# Battery_Charger.net
KiCad netlist of a schematic drawn in Altium Designer
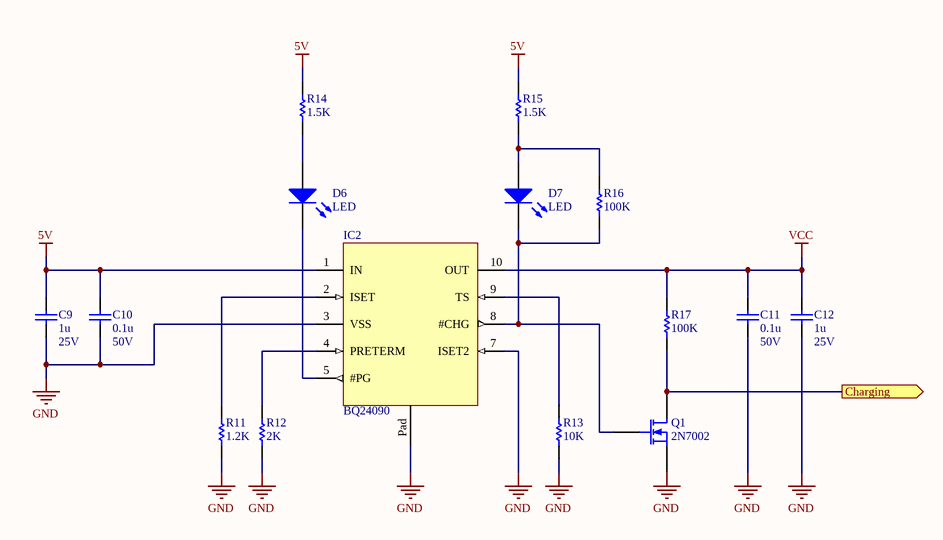
[diagram p0: Battery Charger.SchDoc]

(export (version "E")
  (design (tool "Eeschema 10.0.6"))
  (components
    (comp (ref "C9")
      (value "1u")
      (footprint "C1206")
      (description "Capacitor")
      (fields (field (name "RATED VOLTAGE") "25V"))
      (libsource (lib "Common Devices") (part "Capacitor"))
    )
    (comp (ref "C10")
      (value "0.1u")
      (footprint "C1206")
      (description "Capacitor")
      (fields (field (name "RATED VOLTAGE") "50V"))
      (libsource (lib "Common Devices") (part "Capacitor"))
    )
    (comp (ref "C11")
      (value "0.1u")
      (footprint "C1206")
      (description "Capacitor")
      (fields (field (name "RATED VOLTAGE") "50V"))
      (libsource (lib "Common Devices") (part "Capacitor"))
    )
    (comp (ref "C12")
      (value "1u")
      (footprint "C1206")
      (description "Capacitor")
      (fields (field (name "RATED VOLTAGE") "25V"))
      (libsource (lib "Common Devices") (part "Capacitor"))
    )
    (comp (ref "D6") (value "LED") (footprint "LED3015M") (libsource (lib "Common Devices") (part "LED")))
    (comp (ref "D7") (value "LED") (footprint "LED3015M") (libsource (lib "Common Devices") (part "LED")))
    (comp (ref "IC2")
      (value "BQ24090")
      (footprint "TSSOP50P490X110_HS-11N")
      (description "Battery Charger, Single Cell Li-Ion/LiPo, 1A")
      (libsource (lib "Docking Station") (part "BQ24090"))
    )
    (comp (ref "Q1")
      (value "2N7002")
      (footprint "SOT65P210X110-3N")
      (description "Transistor, MOSFET, N-Channel, 60V, 300mA")
      (libsource (lib "Common Devices") (part "2N7002"))
    )
    (comp (ref "R11")
      (value "1.2K")
      (footprint "R1206")
      (description "Resistor")
      (libsource (lib "Common Devices") (part "Resistor"))
    )
    (comp (ref "R12")
      (value "2K")
      (footprint "R1206")
      (description "Resistor")
      (libsource (lib "Common Devices") (part "Resistor"))
    )
    (comp (ref "R13")
      (value "10K")
      (footprint "R1206")
      (description "Resistor")
      (libsource (lib "Common Devices") (part "Resistor"))
    )
    (comp (ref "R14")
      (value "1.5K")
      (footprint "R1206")
      (description "Resistor")
      (libsource (lib "Common Devices") (part "Resistor"))
    )
    (comp (ref "R15")
      (value "1.5K")
      (footprint "R1206")
      (description "Resistor")
      (libsource (lib "Common Devices") (part "Resistor"))
    )
    (comp (ref "R16")
      (value "100K")
      (footprint "R1206")
      (description "Resistor")
      (libsource (lib "Common Devices") (part "Resistor"))
    )
    (comp (ref "R17")
      (value "100K")
      (footprint "R1206")
      (description "Resistor")
      (libsource (lib "Common Devices") (part "Resistor"))
    )
  )
  (nets
    (net (code "1") (name "/Charging") (class "Default")
      (node (ref "Q1") (pin "3") (pinfunction "D_3") (pintype "passive"))
      (node (ref "R17") (pin "1") (pinfunction "1_1") (pintype "passive"))
    )
    (net (code "2") (name "5V") (class "Default")
      (node (ref "C10") (pin "2") (pinfunction "2_2") (pintype "passive"))
      (node (ref "C9") (pin "2") (pinfunction "2_2") (pintype "passive"))
      (node (ref "IC2") (pin "1") (pinfunction "IN_1") (pintype "power_in"))
      (node (ref "R14") (pin "2") (pinfunction "2_2") (pintype "passive"))
      (node (ref "R15") (pin "2") (pinfunction "2_2") (pintype "passive"))
    )
    (net (code "3") (name "GND") (class "Default")
      (node (ref "C10") (pin "1") (pinfunction "1_1") (pintype "passive"))
      (node (ref "C11") (pin "1") (pinfunction "1_1") (pintype "passive"))
      (node (ref "C12") (pin "1") (pinfunction "1_1") (pintype "passive"))
      (node (ref "C9") (pin "1") (pinfunction "1_1") (pintype "passive"))
      (node (ref "IC2") (pin "3") (pinfunction "VSS_3") (pintype "power_in"))
      (node (ref "IC2") (pin "7") (pinfunction "ISET2_7") (pintype "input"))
      (node (ref "IC2") (pin "Pad") (pinfunction "Thermal_Pad") (pintype "passive"))
      (node (ref "Q1") (pin "2") (pinfunction "S_2") (pintype "passive"))
      (node (ref "R11") (pin "1") (pinfunction "1_1") (pintype "passive"))
      (node (ref "R12") (pin "1") (pinfunction "1_1") (pintype "passive"))
      (node (ref "R13") (pin "1") (pinfunction "1_1") (pintype "passive"))
    )
    (net (code "4") (name "Net-(D6-A)") (class "Default")
      (node (ref "D6") (pin "1") (pinfunction "A_1") (pintype "passive"))
      (node (ref "R14") (pin "1") (pinfunction "1_1") (pintype "passive"))
    )
    (net (code "5") (name "Net-(D6-K)") (class "Default")
      (node (ref "D6") (pin "2") (pinfunction "K_2") (pintype "passive"))
      (node (ref "IC2") (pin "5") (pinfunction "#PG_5") (pintype "output"))
    )
    (net (code "6") (name "Net-(D7-A)") (class "Default")
      (node (ref "D7") (pin "1") (pinfunction "A_1") (pintype "passive"))
      (node (ref "R15") (pin "1") (pinfunction "1_1") (pintype "passive"))
      (node (ref "R16") (pin "2") (pinfunction "2_2") (pintype "passive"))
    )
    (net (code "7") (name "Net-(D7-K)") (class "Default")
      (node (ref "D7") (pin "2") (pinfunction "K_2") (pintype "passive"))
      (node (ref "IC2") (pin "8") (pinfunction "#CHG_8") (pintype "output"))
      (node (ref "Q1") (pin "1") (pinfunction "G_1") (pintype "passive"))
      (node (ref "R16") (pin "1") (pinfunction "1_1") (pintype "passive"))
    )
    (net (code "8") (name "Net-(IC2-ISET)") (class "Default")
      (node (ref "IC2") (pin "2") (pinfunction "ISET_2") (pintype "input"))
      (node (ref "R11") (pin "2") (pinfunction "2_2") (pintype "passive"))
    )
    (net (code "9") (name "Net-(IC2-PRETERM)") (class "Default")
      (node (ref "IC2") (pin "4") (pinfunction "PRETERM_4") (pintype "input"))
      (node (ref "R12") (pin "2") (pinfunction "2_2") (pintype "passive"))
    )
    (net (code "10") (name "Net-(IC2-TS)") (class "Default")
      (node (ref "IC2") (pin "9") (pinfunction "TS_9") (pintype "input"))
      (node (ref "R13") (pin "2") (pinfunction "2_2") (pintype "passive"))
    )
    (net (code "11") (name "VCC") (class "Default")
      (node (ref "C11") (pin "2") (pinfunction "2_2") (pintype "passive"))
      (node (ref "C12") (pin "2") (pinfunction "2_2") (pintype "passive"))
      (node (ref "IC2") (pin "10") (pinfunction "OUT_10") (pintype "power_in"))
      (node (ref "R17") (pin "2") (pinfunction "2_2") (pintype "passive"))
    )
  )
)
